# ArduinoPB-Pro-Mini.net
KiCad netlist of a schematic drawn in EAGLE
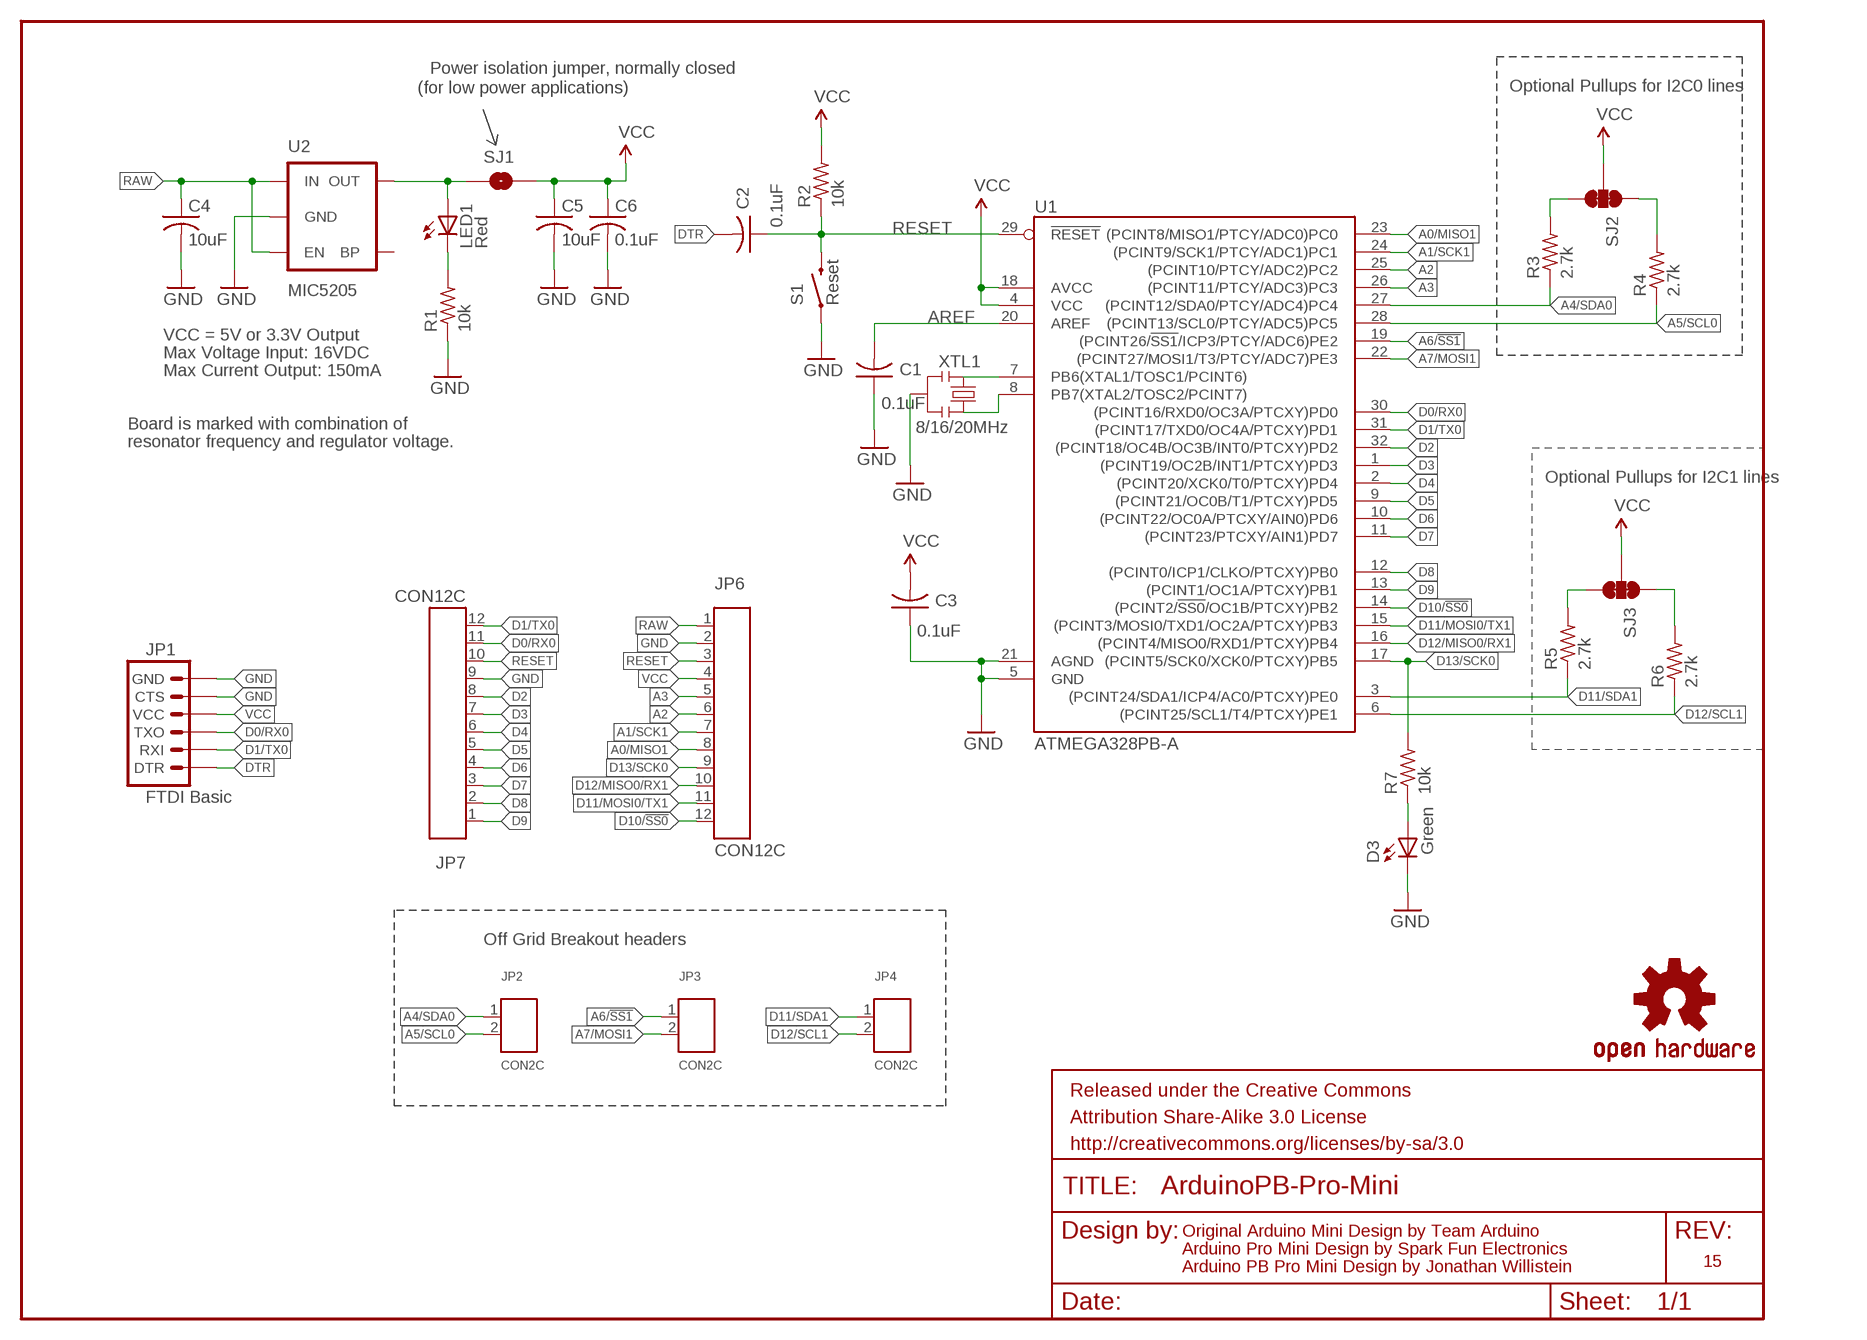
[diagram p0: schematic, sheet 1]

(export (version "E")
  (design (tool "Eeschema 10.0.6"))
  (components
    (comp (ref "C1")
      (value "0.1uF")
      (footprint "eagle-import:C0603")
      (libsource (lib "eagle-import") (part "C-USC0603"))
    )
    (comp (ref "C2")
      (value "0.1uF")
      (footprint "eagle-import:C0603")
      (libsource (lib "eagle-import") (part "C-USC0603"))
    )
    (comp (ref "C3")
      (value "0.1uF")
      (footprint "eagle-import:C0603")
      (libsource (lib "eagle-import") (part "C-USC0603"))
    )
    (comp (ref "C4")
      (value "10uF")
      (footprint "eagle-import:C0805")
      (libsource (lib "eagle-import") (part "C-USC0805"))
    )
    (comp (ref "C5")
      (value "10uF")
      (footprint "eagle-import:C0805")
      (libsource (lib "eagle-import") (part "C-USC0805"))
    )
    (comp (ref "C6")
      (value "0.1uF")
      (footprint "eagle-import:C0603")
      (libsource (lib "eagle-import") (part "C-USC0603"))
    )
    (comp (ref "D3")
      (value "Green")
      (footprint "eagle-import:0603-LED-ALT1")
      (libsource (lib "eagle-import") (part "LED"))
    )
    (comp (ref "FRAME1")
      (value "FRAME-LETTER")
      (footprint "eagle-import:CREATIVE_COMMONS")
      (libsource (lib "eagle-import") (part "FRAME-LETTER"))
    )
    (comp (ref "JP1")
      (value "FTDI Basic")
      (footprint "eagle-import:1X6C")
      (libsource (lib "eagle-import") (part "ARDUINO_SERIAL_PROGRAM"))
    )
    (comp (ref "JP2")
      (value "CON2C")
      (footprint "eagle-import:1X2C")
      (libsource (lib "eagle-import") (part "CON2C"))
    )
    (comp (ref "JP3")
      (value "CON2C")
      (footprint "eagle-import:1X2C")
      (libsource (lib "eagle-import") (part "CON2C"))
    )
    (comp (ref "JP4")
      (value "CON2C")
      (footprint "eagle-import:1X2C")
      (libsource (lib "eagle-import") (part "CON2C"))
    )
    (comp (ref "JP6")
      (value "CON12C")
      (footprint "eagle-import:1X12C")
      (libsource (lib "eagle-import") (part "CON12C"))
    )
    (comp (ref "JP7")
      (value "CON12C")
      (footprint "eagle-import:1X12C")
      (libsource (lib "eagle-import") (part "CON12C"))
    )
    (comp (ref "LED1")
      (value "Red")
      (footprint "eagle-import:0603-LED-ALT1")
      (libsource (lib "eagle-import") (part "LED"))
    )
    (comp (ref "R1")
      (value "10k")
      (footprint "eagle-import:R0603")
      (libsource (lib "eagle-import") (part "R-US_R0603"))
    )
    (comp (ref "R2")
      (value "10k")
      (footprint "eagle-import:R0603")
      (libsource (lib "eagle-import") (part "R-US_R0603"))
    )
    (comp (ref "R3")
      (value "2.7k")
      (footprint "eagle-import:R0603")
      (libsource (lib "eagle-import") (part "R-US_R0603"))
    )
    (comp (ref "R4")
      (value "2.7k")
      (footprint "eagle-import:R0603")
      (libsource (lib "eagle-import") (part "R-US_R0603"))
    )
    (comp (ref "R5")
      (value "2.7k")
      (footprint "eagle-import:R0603")
      (libsource (lib "eagle-import") (part "R-US_R0603"))
    )
    (comp (ref "R6")
      (value "2.7k")
      (footprint "eagle-import:R0603")
      (libsource (lib "eagle-import") (part "R-US_R0603"))
    )
    (comp (ref "R7")
      (value "10k")
      (footprint "eagle-import:R0603")
      (libsource (lib "eagle-import") (part "R-US_R0603"))
    )
    (comp (ref "S1")
      (value "Reset")
      (footprint "eagle-import:TACTILE-SWITCH-SMD-ALT01")
      (libsource (lib "eagle-import") (part "SWITCH-MOMENTARY-2SMD-ALT01"))
    )
    (comp (ref "SJ1")
      (value "SOLDERJUMPERTRACE")
      (footprint "eagle-import:SJ_2S-TRACE")
      (libsource (lib "eagle-import") (part "SOLDERJUMPERTRACE"))
    )
    (comp (ref "SJ2")
      (value "JUMPER-PAD-3-NC_BY_TRACE")
      (footprint "eagle-import:PAD-JUMPER-3-3OF3_NC_BY_TRACE_YES_SILK_FULL_BOX")
      (libsource (lib "eagle-import") (part "JUMPER-PAD-3-NC_BY_TRACE"))
    )
    (comp (ref "SJ3")
      (value "JUMPER-PAD-3-NC_BY_TRACE")
      (footprint "eagle-import:PAD-JUMPER-3-3OF3_NC_BY_TRACE_YES_SILK_FULL_BOX")
      (libsource (lib "eagle-import") (part "JUMPER-PAD-3-NC_BY_TRACE"))
    )
    (comp (ref "U$3")
      (value "OSHW-LOGOS")
      (footprint "eagle-import:OSHW-LOGO-S")
      (libsource (lib "eagle-import") (part "OSHW-LOGOS"))
    )
    (comp (ref "U1")
      (value "ATMEGA328PB-A")
      (footprint "eagle-import:TQFP32-08")
      (libsource (lib "eagle-import") (part "ATMEGA328PB-?A"))
    )
    (comp (ref "U2")
      (value "MIC5205")
      (footprint "eagle-import:SOT23-5")
      (libsource (lib "eagle-import") (part "V_REG_LDOSMD"))
    )
    (comp (ref "XTL1")
      (value "8/16/20MHz")
      (footprint "eagle-import:RESONATOR-SMD-1_1")
      (libsource (lib "eagle-import") (part "RESONATOR1{colon}1"))
    )
  )
  (nets
    (net (code "1") (name "/A6{slash}~{SS1}") (class "Default")
      (node (ref "JP3") (pin "1") (pinfunction "P$1_1") (pintype "bidirectional"))
      (node (ref "U1") (pin "19") (pinfunction "(PCINT26/~{SS1}/ICP3/PTCY/ADC6)PE2_19") (pintype "bidirectional"))
    )
    (net (code "2") (name "/AREF") (class "Default")
      (node (ref "C1") (pin "2") (pinfunction "2_2") (pintype "passive"))
      (node (ref "U1") (pin "20") (pinfunction "AREF_20") (pintype "bidirectional"))
    )
    (net (code "3") (name "/D10{slash}~{SS0}") (class "Default")
      (node (ref "JP6") (pin "12") (pinfunction "12_12") (pintype "bidirectional"))
      (node (ref "U1") (pin "14") (pinfunction "(PCINT2/~{SS0}/OC1B/PTCXY)PB2_14") (pintype "bidirectional"))
    )
    (net (code "4") (name "A0{slash}MISO1") (class "Default")
      (node (ref "JP6") (pin "8") (pinfunction "8_8") (pintype "bidirectional"))
      (node (ref "U1") (pin "23") (pinfunction "(PCINT8/MISO1/PTCY/ADC0)PC0_23") (pintype "bidirectional"))
    )
    (net (code "5") (name "A1{slash}SCK1") (class "Default")
      (node (ref "JP6") (pin "7") (pinfunction "7_7") (pintype "bidirectional"))
      (node (ref "U1") (pin "24") (pinfunction "(PCINT9/SCK1/PTCY/ADC1)PC1_24") (pintype "bidirectional"))
    )
    (net (code "6") (name "A2") (class "Default")
      (node (ref "JP6") (pin "6") (pinfunction "6_6") (pintype "bidirectional"))
      (node (ref "U1") (pin "25") (pinfunction "(PCINT10/PTCY/ADC2)PC2_25") (pintype "bidirectional"))
    )
    (net (code "7") (name "A3") (class "Default")
      (node (ref "JP6") (pin "5") (pinfunction "5_5") (pintype "bidirectional"))
      (node (ref "U1") (pin "26") (pinfunction "(PCINT11/PTCY/ADC3)PC3_26") (pintype "bidirectional"))
    )
    (net (code "8") (name "A4{slash}SDA0") (class "Default")
      (node (ref "JP2") (pin "1") (pinfunction "P$1_1") (pintype "bidirectional"))
      (node (ref "R3") (pin "1") (pinfunction "1_1") (pintype "passive"))
      (node (ref "U1") (pin "27") (pinfunction "(PCINT12/SDA0/PTCY/ADC4)PC4_27") (pintype "bidirectional"))
    )
    (net (code "9") (name "A5{slash}SCL0") (class "Default")
      (node (ref "JP2") (pin "2") (pinfunction "P$2_2") (pintype "bidirectional"))
      (node (ref "R4") (pin "1") (pinfunction "1_1") (pintype "passive"))
      (node (ref "U1") (pin "28") (pinfunction "(PCINT13/SCL0/PTCY/ADC5)PC5_28") (pintype "bidirectional"))
    )
    (net (code "10") (name "A7{slash}MOSI1") (class "Default")
      (node (ref "JP3") (pin "2") (pinfunction "P$2_2") (pintype "bidirectional"))
      (node (ref "U1") (pin "22") (pinfunction "(PCINT27/MOSI1/T3/PTCY/ADC7)PE3_22") (pintype "bidirectional"))
    )
    (net (code "11") (name "D0{slash}RX0") (class "Default")
      (node (ref "JP1") (pin "3") (pinfunction "TXO_3") (pintype "passive"))
      (node (ref "JP7") (pin "11") (pinfunction "11_11") (pintype "bidirectional"))
      (node (ref "U1") (pin "30") (pinfunction "(PCINT16/RXD0/OC3A/PTCXY)PD0_30") (pintype "bidirectional"))
    )
    (net (code "12") (name "D1{slash}TX0") (class "Default")
      (node (ref "JP1") (pin "2") (pinfunction "RXI_2") (pintype "passive"))
      (node (ref "JP7") (pin "12") (pinfunction "12_12") (pintype "bidirectional"))
      (node (ref "U1") (pin "31") (pinfunction "(PCINT17/TXD0/OC4A/PTCXY)PD1_31") (pintype "bidirectional"))
    )
    (net (code "13") (name "D2") (class "Default")
      (node (ref "JP7") (pin "8") (pinfunction "8_8") (pintype "bidirectional"))
      (node (ref "U1") (pin "32") (pinfunction "(PCINT18/OC4B/OC3B/INT0/PTCXY)PD2_32") (pintype "bidirectional"))
    )
    (net (code "14") (name "D3") (class "Default")
      (node (ref "JP7") (pin "7") (pinfunction "7_7") (pintype "bidirectional"))
      (node (ref "U1") (pin "1") (pinfunction "(PCINT19/OC2B/INT1/PTCXY)PD3_1") (pintype "bidirectional"))
    )
    (net (code "15") (name "D4") (class "Default")
      (node (ref "JP7") (pin "6") (pinfunction "6_6") (pintype "bidirectional"))
      (node (ref "U1") (pin "2") (pinfunction "(PCINT20/XCK0/T0/PTCXY)PD4_2") (pintype "bidirectional"))
    )
    (net (code "16") (name "D5") (class "Default")
      (node (ref "JP7") (pin "5") (pinfunction "5_5") (pintype "bidirectional"))
      (node (ref "U1") (pin "9") (pinfunction "(PCINT21/OC0B/T1/PTCXY)PD5_9") (pintype "bidirectional"))
    )
    (net (code "17") (name "D6") (class "Default")
      (node (ref "JP7") (pin "4") (pinfunction "4_4") (pintype "bidirectional"))
      (node (ref "U1") (pin "10") (pinfunction "(PCINT22/OC0A/PTCXY/AIN0)PD6_10") (pintype "bidirectional"))
    )
    (net (code "18") (name "D7") (class "Default")
      (node (ref "JP7") (pin "3") (pinfunction "3_3") (pintype "bidirectional"))
      (node (ref "U1") (pin "11") (pinfunction "(PCINT23/PTCXY/AIN1)PD7_11") (pintype "bidirectional"))
    )
    (net (code "19") (name "D8") (class "Default")
      (node (ref "JP7") (pin "2") (pinfunction "2_2") (pintype "bidirectional"))
      (node (ref "U1") (pin "12") (pinfunction "(PCINT0/ICP1/CLKO/PTCXY)PB0_12") (pintype "bidirectional"))
    )
    (net (code "20") (name "D9") (class "Default")
      (node (ref "JP7") (pin "1") (pinfunction "1_1") (pintype "bidirectional"))
      (node (ref "U1") (pin "13") (pinfunction "(PCINT1/OC1A/PTCXY)PB1_13") (pintype "bidirectional"))
    )
    (net (code "21") (name "D11{slash}MOSI0{slash}TX1") (class "Default")
      (node (ref "JP6") (pin "11") (pinfunction "11_11") (pintype "bidirectional"))
      (node (ref "U1") (pin "15") (pinfunction "(PCINT3/MOSI0/TXD1/OC2A/PTCXY)PB3_15") (pintype "bidirectional"))
    )
    (net (code "22") (name "D11{slash}SDA1") (class "Default")
      (node (ref "JP4") (pin "1") (pinfunction "P$1_1") (pintype "bidirectional"))
      (node (ref "R5") (pin "1") (pinfunction "1_1") (pintype "passive"))
      (node (ref "U1") (pin "3") (pinfunction "(PCINT24/SDA1/ICP4/AC0/PTCXY)PE0_3") (pintype "bidirectional"))
    )
    (net (code "23") (name "D12{slash}MISO0{slash}RX1") (class "Default")
      (node (ref "JP6") (pin "10") (pinfunction "10_10") (pintype "bidirectional"))
      (node (ref "U1") (pin "16") (pinfunction "(PCINT4/MISO0/RXD1/PTCXY)PB4_16") (pintype "bidirectional"))
    )
    (net (code "24") (name "D12{slash}SCL1") (class "Default")
      (node (ref "JP4") (pin "2") (pinfunction "P$2_2") (pintype "bidirectional"))
      (node (ref "R6") (pin "1") (pinfunction "1_1") (pintype "passive"))
      (node (ref "U1") (pin "6") (pinfunction "(PCINT25/SCL1/T4/PTCXY)PE1_6") (pintype "bidirectional"))
    )
    (net (code "25") (name "D13{slash}SCK0") (class "Default")
      (node (ref "JP6") (pin "9") (pinfunction "9_9") (pintype "bidirectional"))
      (node (ref "R7") (pin "2") (pinfunction "2_2") (pintype "passive"))
      (node (ref "U1") (pin "17") (pinfunction "(PCINT5/SCK0/XCK0/PTCXY)PB5_17") (pintype "bidirectional"))
    )
    (net (code "26") (name "DTR") (class "Default")
      (node (ref "C2") (pin "2") (pinfunction "2_2") (pintype "passive"))
      (node (ref "JP1") (pin "1") (pinfunction "DTR_1") (pintype "passive"))
    )
    (net (code "27") (name "GND") (class "Default")
      (node (ref "C1") (pin "1") (pinfunction "1_1") (pintype "passive"))
      (node (ref "C3") (pin "1") (pinfunction "1_1") (pintype "passive"))
      (node (ref "C4") (pin "2") (pinfunction "2_2") (pintype "passive"))
      (node (ref "C5") (pin "2") (pinfunction "2_2") (pintype "passive"))
      (node (ref "C6") (pin "2") (pinfunction "2_2") (pintype "passive"))
      (node (ref "D3") (pin "C") (pinfunction "C_C") (pintype "passive"))
      (node (ref "JP1") (pin "5") (pinfunction "CTS_5") (pintype "passive"))
      (node (ref "JP1") (pin "6") (pinfunction "GND_6") (pintype "passive"))
      (node (ref "JP6") (pin "2") (pinfunction "2_2") (pintype "bidirectional"))
      (node (ref "JP7") (pin "9") (pinfunction "9_9") (pintype "bidirectional"))
      (node (ref "R1") (pin "1") (pinfunction "1_1") (pintype "passive"))
      (node (ref "S1") (pin "1") (pinfunction "1_1") (pintype "passive"))
      (node (ref "S1") (pin "2") (pinfunction "1_2") (pintype "passive"))
      (node (ref "U1") (pin "21") (pinfunction "AGND_21") (pintype "power_in"))
      (node (ref "U1") (pin "5") (pinfunction "GND_5") (pintype "power_in"))
      (node (ref "U2") (pin "2") (pinfunction "GND_2") (pintype "input"))
      (node (ref "XTL1") (pin "2") (pinfunction "2_2") (pintype "passive"))
    )
    (net (code "28") (name "Net-(D3-PadA)") (class "Default")
      (node (ref "D3") (pin "A") (pinfunction "A_A") (pintype "passive"))
      (node (ref "R7") (pin "1") (pinfunction "1_1") (pintype "passive"))
    )
    (net (code "29") (name "Net-(LED1-PadC)") (class "Default")
      (node (ref "LED1") (pin "C") (pinfunction "C_C") (pintype "passive"))
      (node (ref "R1") (pin "2") (pinfunction "2_2") (pintype "passive"))
    )
    (net (code "30") (name "Net-(R3-Pad2)") (class "Default")
      (node (ref "R3") (pin "2") (pinfunction "2_2") (pintype "passive"))
      (node (ref "SJ2") (pin "3") (pinfunction "3_3") (pintype "passive"))
    )
    (net (code "31") (name "Net-(R4-Pad2)") (class "Default")
      (node (ref "R4") (pin "2") (pinfunction "2_2") (pintype "passive"))
      (node (ref "SJ2") (pin "1") (pinfunction "1_1") (pintype "passive"))
    )
    (net (code "32") (name "Net-(R5-Pad2)") (class "Default")
      (node (ref "R5") (pin "2") (pinfunction "2_2") (pintype "passive"))
      (node (ref "SJ3") (pin "3") (pinfunction "3_3") (pintype "passive"))
    )
    (net (code "33") (name "Net-(R6-Pad2)") (class "Default")
      (node (ref "R6") (pin "2") (pinfunction "2_2") (pintype "passive"))
      (node (ref "SJ3") (pin "1") (pinfunction "1_1") (pintype "passive"))
    )
    (net (code "34") (name "Net-(U1-PB6(XTAL1{slash}TOSC1{slash}PCINT6))") (class "Default")
      (node (ref "U1") (pin "7") (pinfunction "PB6(XTAL1/TOSC1/PCINT6)_7") (pintype "bidirectional"))
      (node (ref "XTL1") (pin "1") (pinfunction "1_1") (pintype "passive"))
    )
    (net (code "35") (name "Net-(U1-PB7(XTAL2{slash}TOSC2{slash}PCINT7))") (class "Default")
      (node (ref "U1") (pin "8") (pinfunction "PB7(XTAL2/TOSC2/PCINT7)_8") (pintype "bidirectional"))
      (node (ref "XTL1") (pin "3") (pinfunction "3_3") (pintype "passive"))
    )
    (net (code "36") (name "Net-(U2-OUT)") (class "Default")
      (node (ref "LED1") (pin "A") (pinfunction "A_A") (pintype "passive"))
      (node (ref "SJ1") (pin "1") (pinfunction "1_1") (pintype "passive"))
      (node (ref "U2") (pin "5") (pinfunction "OUT_5") (pintype "passive"))
    )
    (net (code "37") (name "RAW") (class "Default")
      (node (ref "C4") (pin "1") (pinfunction "1_1") (pintype "passive"))
      (node (ref "JP6") (pin "1") (pinfunction "1_1") (pintype "bidirectional"))
      (node (ref "U2") (pin "1") (pinfunction "IN_1") (pintype "input"))
      (node (ref "U2") (pin "3") (pinfunction "EN_3") (pintype "input"))
    )
    (net (code "38") (name "RESET") (class "Default")
      (node (ref "C2") (pin "1") (pinfunction "1_1") (pintype "passive"))
      (node (ref "JP6") (pin "3") (pinfunction "3_3") (pintype "bidirectional"))
      (node (ref "JP7") (pin "10") (pinfunction "10_10") (pintype "bidirectional"))
      (node (ref "R2") (pin "1") (pinfunction "1_1") (pintype "passive"))
      (node (ref "S1") (pin "3") (pinfunction "2_3") (pintype "passive"))
      (node (ref "S1") (pin "4") (pinfunction "2_4") (pintype "passive"))
      (node (ref "U1") (pin "29") (pinfunction "~{RESET}_29") (pintype "bidirectional"))
    )
    (net (code "39") (name "VCC") (class "Default")
      (node (ref "C3") (pin "2") (pinfunction "2_2") (pintype "passive"))
      (node (ref "C5") (pin "1") (pinfunction "1_1") (pintype "passive"))
      (node (ref "C6") (pin "1") (pinfunction "1_1") (pintype "passive"))
      (node (ref "JP1") (pin "4") (pinfunction "VCC_4") (pintype "passive"))
      (node (ref "JP6") (pin "4") (pinfunction "4_4") (pintype "bidirectional"))
      (node (ref "R2") (pin "2") (pinfunction "2_2") (pintype "passive"))
      (node (ref "SJ1") (pin "2") (pinfunction "2_2") (pintype "passive"))
      (node (ref "SJ2") (pin "2") (pinfunction "2_2") (pintype "passive"))
      (node (ref "SJ3") (pin "2") (pinfunction "2_2") (pintype "passive"))
      (node (ref "U1") (pin "18") (pinfunction "AVCC_18") (pintype "bidirectional"))
      (node (ref "U1") (pin "4") (pinfunction "VCC_4") (pintype "power_in"))
    )
    (net (code "40") (name "unconnected-(U2-BP-Pad4)") (class "Default")
      (node (ref "U2") (pin "4") (pinfunction "BP_4") (pintype "input"))
    )
  )
)
